# Common.net
KiCad netlist of a schematic drawn in Altium Designer
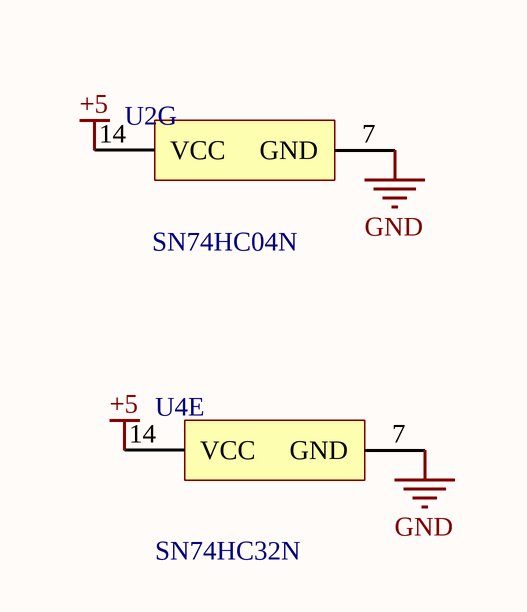
[diagram p0: Common.SchDoc]

(export (version "E")
  (design (tool "Eeschema 10.0.6"))
  (components
    (comp (ref "U2")
      (value "SN74HC04N")
      (footprint "N0014A")
      (description "Hex Inverters, N0014A, TUBE")
      (fields
        (field (name "MANUFACTURER") "Texas Instruments")
        (field (name "GENERIC PART NUMBER") "SN74HC04")
      )
      (libsource (lib "Altium Content Vault") (part "TI-CD_SNX4XXXXXX4X_19A-14"))
    )
    (comp (ref "U4")
      (value "SN74HC32N")
      (footprint "N0014A")
      (description "Quadruple 2-Input Positive-OR Gates, N0014A, TUBE")
      (fields
        (field (name "MANUFACTURER") "Texas Instruments")
        (field (name "GENERIC PART NUMBER") "SN74HC32")
      )
      (libsource (lib "Altium Content Vault") (part "TI-OR-4-2IN-14"))
    )
  )
  (nets
    (net (code "1") (name "+5") (class "Default")
      (node (ref "U2") (pin "14") (pinfunction "VCC_14") (pintype "power_in"))
      (node (ref "U4") (pin "14") (pinfunction "VCC_14") (pintype "power_in"))
    )
    (net (code "2") (name "GND") (class "Default")
      (node (ref "U2") (pin "7") (pinfunction "GND_7") (pintype "power_in"))
      (node (ref "U4") (pin "7") (pinfunction "GND_7") (pintype "power_in"))
    )
  )
)
